# controller.net
KiCad netlist of a schematic drawn in EAGLE
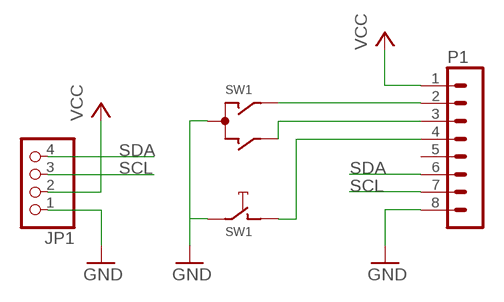
[diagram p0: schematic, sheet 1]

(export (version "E")
  (design (tool "Eeschema 10.0.6"))
  (components
    (comp (ref "JP1")
      (value "PINHD-1X4")
      (footprint "eagle-import:1X04")
      (libsource (lib "eagle-import") (part "PINHD-1X4"))
    )
    (comp (ref "P1")
      (value "B8B-PH-K")
      (footprint "eagle-import:B8B-PH-K")
      (libsource (lib "eagle-import") (part "B8B-PH-K"))
    )
    (comp (ref "SW1")
      (value "OG-ENCODER_EC12E_SW")
      (footprint "eagle-import:OG-ENCODER_ALPS_EC12E_SW")
      (libsource (lib "eagle-import") (part "OG-ENCODER_EC12E_SW"))
    )
  )
  (nets
    (net (code "1") (name "/SCL") (class "Default")
      (node (ref "JP1") (pin "3") (pinfunction "3_3") (pintype "passive"))
      (node (ref "P1") (pin "7") (pinfunction "7_7") (pintype "passive"))
    )
    (net (code "2") (name "/SDA") (class "Default")
      (node (ref "JP1") (pin "4") (pinfunction "4_4") (pintype "passive"))
      (node (ref "P1") (pin "6") (pinfunction "6_6") (pintype "passive"))
    )
    (net (code "3") (name "GND") (class "Default")
      (node (ref "JP1") (pin "1") (pinfunction "1_1") (pintype "passive"))
      (node (ref "P1") (pin "8") (pinfunction "8_8") (pintype "passive"))
      (node (ref "SW1") (pin "C") (pinfunction "C_C") (pintype "passive"))
      (node (ref "SW1") (pin "E") (pinfunction "2_E") (pintype "passive"))
    )
    (net (code "4") (name "Net-(P1-Pad2)") (class "Default")
      (node (ref "P1") (pin "2") (pinfunction "2_2") (pintype "passive"))
      (node (ref "SW1") (pin "A") (pinfunction "A_A") (pintype "passive"))
    )
    (net (code "5") (name "Net-(P1-Pad3)") (class "Default")
      (node (ref "P1") (pin "3") (pinfunction "3_3") (pintype "passive"))
      (node (ref "SW1") (pin "B") (pinfunction "B_B") (pintype "passive"))
    )
    (net (code "6") (name "Net-(SW1B-1)") (class "Default")
      (node (ref "P1") (pin "4") (pinfunction "4_4") (pintype "passive"))
      (node (ref "SW1") (pin "D") (pinfunction "1_D") (pintype "passive"))
    )
    (net (code "7") (name "VCC") (class "Default")
      (node (ref "JP1") (pin "2") (pinfunction "2_2") (pintype "passive"))
      (node (ref "P1") (pin "1") (pinfunction "1_1") (pintype "passive"))
    )
    (net (code "8") (name "unconnected-(P1-Pad5)") (class "Default")
      (node (ref "P1") (pin "5") (pinfunction "5_5") (pintype "passive"))
    )
  )
)
